# Controller_Board_Main.net
KiCad netlist of a schematic drawn in Altium Designer
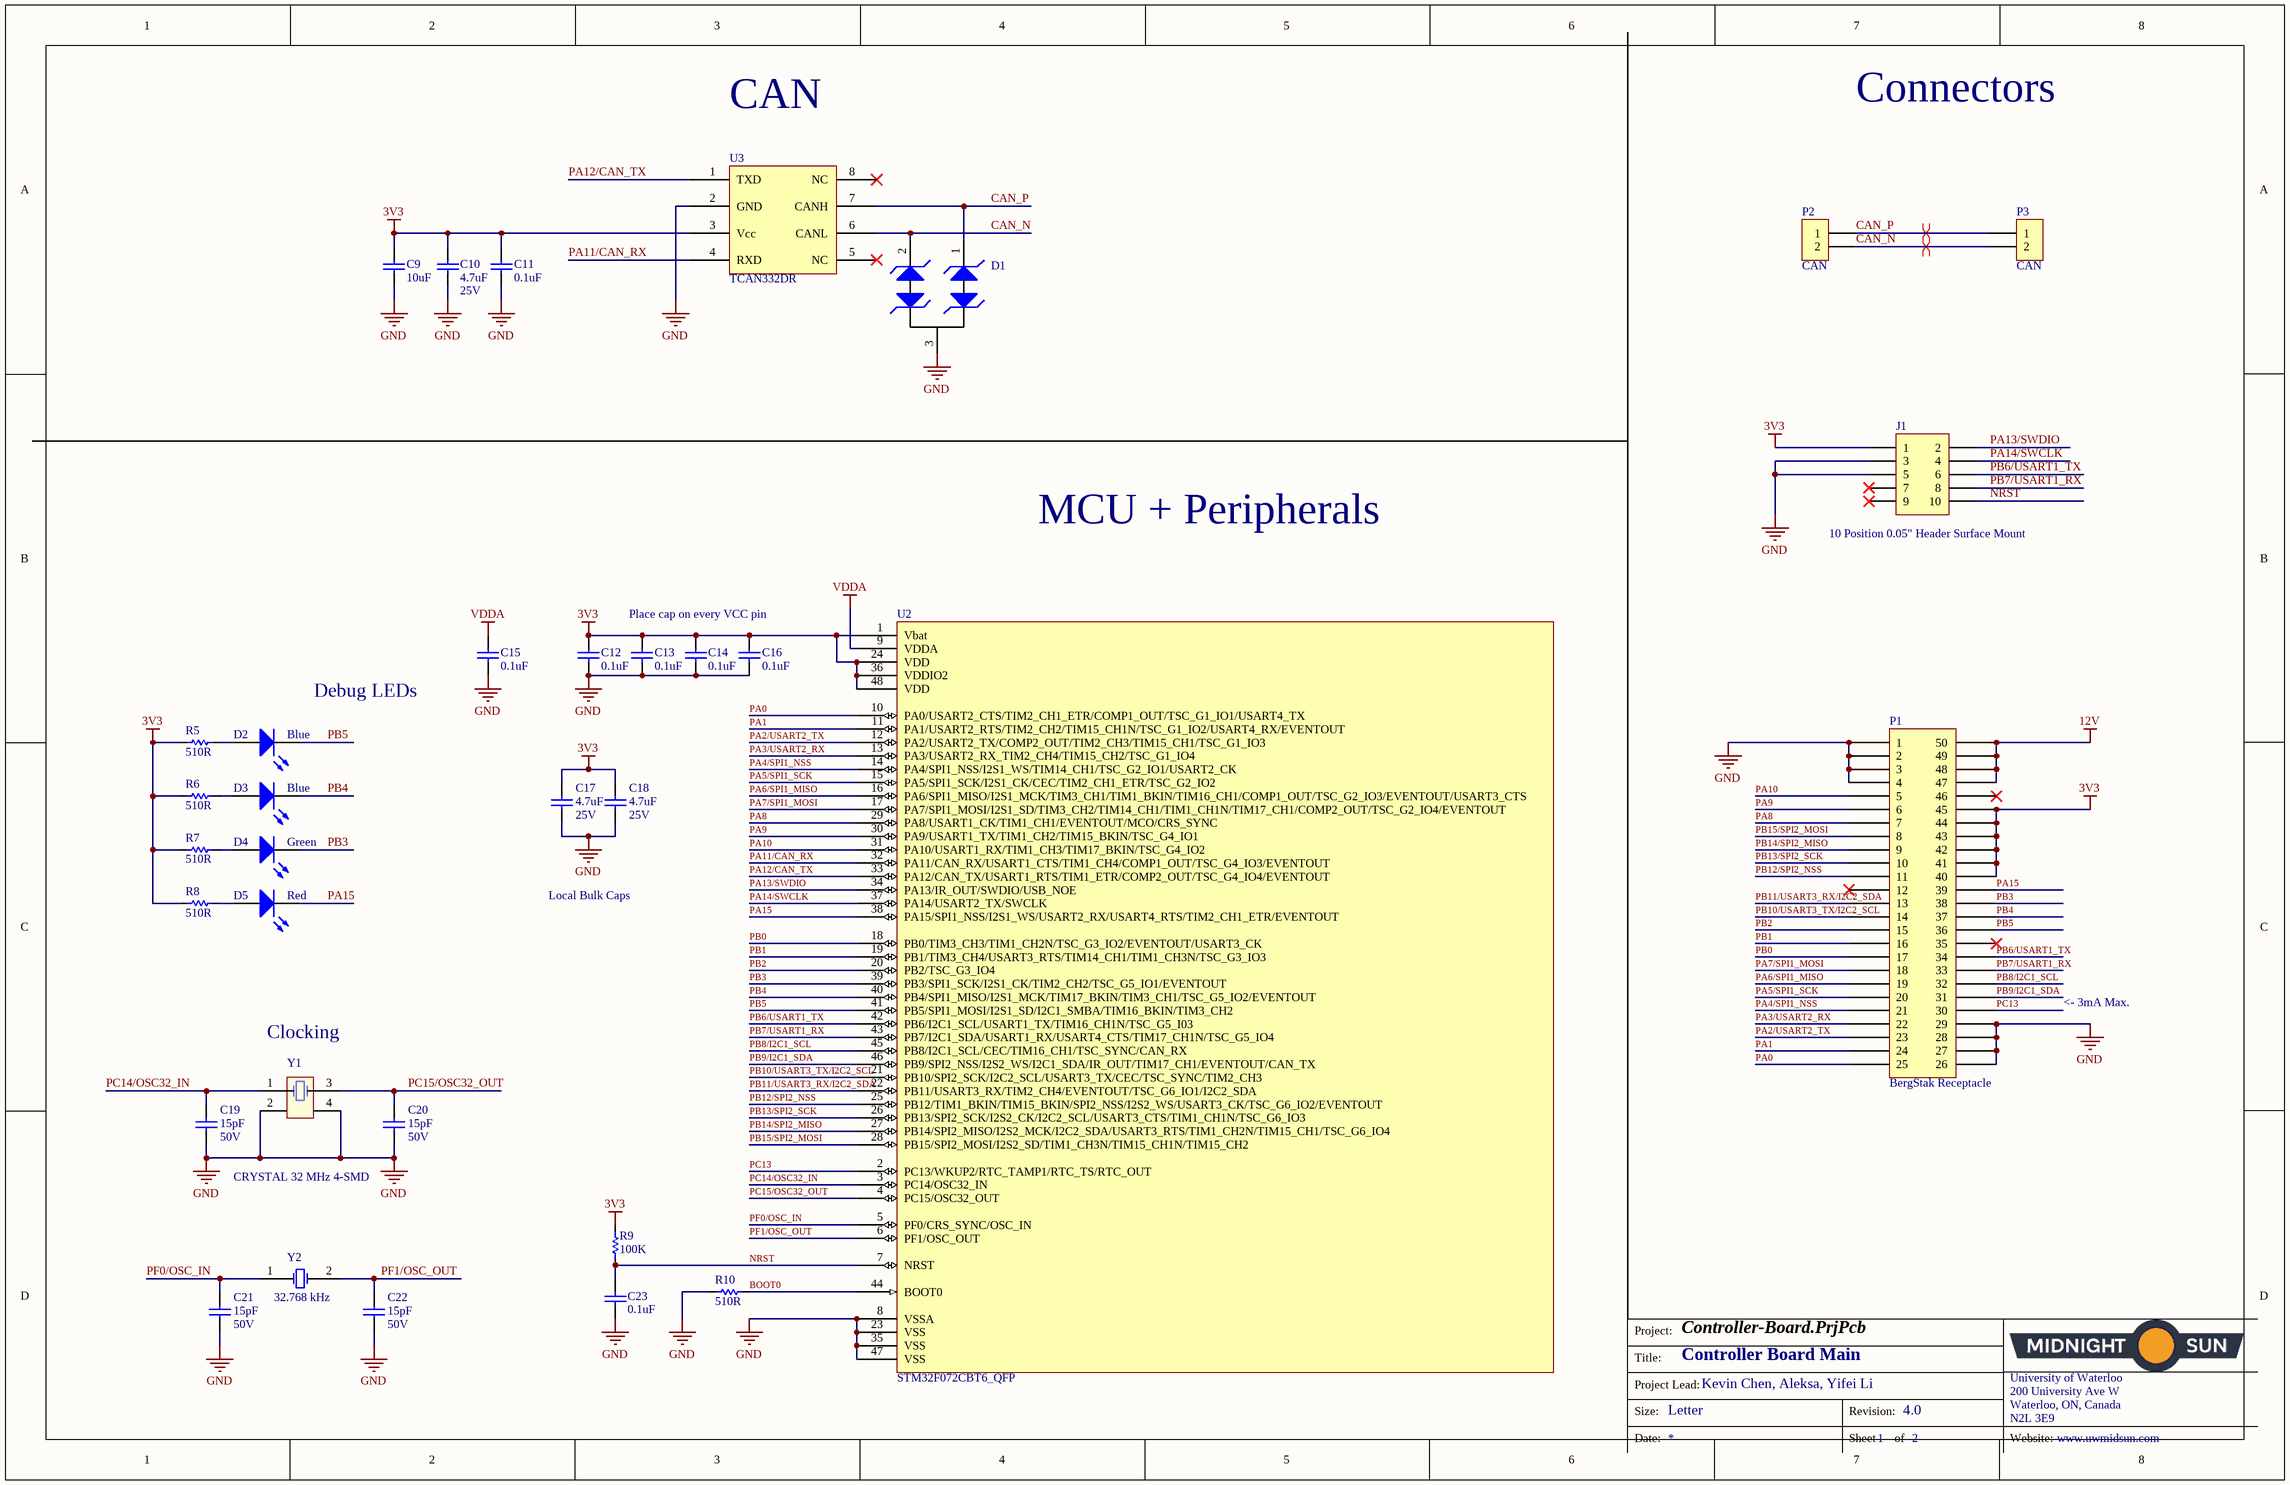
[diagram p0: Controller_Board_Main.SchDoc]

(export (version "E")
  (design (tool "Eeschema 10.0.6"))
  (components
    (comp (ref "C9")
      (value "10uF")
      (footprint "CAPC1608X06N")
      (description "10µF ±20% 25V Ceramic Capacitor X5R 0603 (1608 Metric)")
      (fields
        (field (name "MANUFACTURER") "Murata Electronics North America")
        (field (name "MANUFACTURERPARTNUMBER") "GRM188R61E106MA73D")
      )
      (libsource (lib "Midnight Sun Integrated Library") (part "CAP CER 10uF 25V 20% X5R 0603"))
    )
    (comp (ref "C10")
      (value "4.7uF")
      (footprint "CAPC1608X06N")
      (description "4.7µF ±10% 25V Ceramic Capacitor X5R 0603 (1608 Metric)")
      (fields
        (field (name "MANUFACTURER") "Murata Electronics North America")
        (field (name "MANUFACTURERPARTNUMBER") "GRM188R61E475KE11D")
        (field (name "VOLTAGE") "25V")
      )
      (libsource (lib "Midnight Sun Integrated Library") (part "CAP CER 4.7UF 25V 10% X5R 0603"))
    )
    (comp (ref "C11")
      (value "0.1uF")
      (footprint "CAPC1608X06N")
      (description "0.10µF ±10% 50V Ceramic Capacitor X7R 0603 (1608 Metric)")
      (fields
        (field (name "MANUFACTURER") "AVX Corporation")
        (field (name "MANUFACTURERPARTNUMBER") "06035C104KAT2A")
      )
      (libsource (lib "Midnight Sun Integrated Library") (part "CAP CER 0.1UF 50V 10% X7R 0603"))
    )
    (comp (ref "C12")
      (value "0.1uF")
      (footprint "CAPC1608X06N")
      (description "0.10µF ±10% 50V Ceramic Capacitor X7R 0603 (1608 Metric)")
      (fields
        (field (name "MANUFACTURER") "AVX Corporation")
        (field (name "MANUFACTURERPARTNUMBER") "06035C104KAT2A")
      )
      (libsource (lib "Midnight Sun Integrated Library") (part "CAP CER 0.1UF 50V 10% X7R 0603"))
    )
    (comp (ref "C13")
      (value "0.1uF")
      (footprint "CAPC1608X06N")
      (description "0.10µF ±10% 50V Ceramic Capacitor X7R 0603 (1608 Metric)")
      (fields
        (field (name "MANUFACTURER") "AVX Corporation")
        (field (name "MANUFACTURERPARTNUMBER") "06035C104KAT2A")
      )
      (libsource (lib "Midnight Sun Integrated Library") (part "CAP CER 0.1UF 50V 10% X7R 0603"))
    )
    (comp (ref "C14")
      (value "0.1uF")
      (footprint "CAPC1608X06N")
      (description "0.10µF ±10% 50V Ceramic Capacitor X7R 0603 (1608 Metric)")
      (fields
        (field (name "MANUFACTURER") "AVX Corporation")
        (field (name "MANUFACTURERPARTNUMBER") "06035C104KAT2A")
      )
      (libsource (lib "Midnight Sun Integrated Library") (part "CAP CER 0.1UF 50V 10% X7R 0603"))
    )
    (comp (ref "C15")
      (value "0.1uF")
      (footprint "CAP, 0603")
      (description "0.10µF ±10% 50V Ceramic Capacitor X7R 0603 (1608 Metric)")
      (fields
        (field (name "MANUFACTURER") "AVX Corporation")
        (field (name "MANUFACTURERPARTNUMBER") "06035C104KAT2A")
      )
      (libsource (lib "Midnight Sun Integrated Library") (part "CAP CER 0.1UF 50V 10% X7R 0603"))
    )
    (comp (ref "C16")
      (value "0.1uF")
      (footprint "CAPC1608X06N")
      (description "0.10µF ±10% 50V Ceramic Capacitor X7R 0603 (1608 Metric)")
      (fields
        (field (name "MANUFACTURER") "AVX Corporation")
        (field (name "MANUFACTURERPARTNUMBER") "06035C104KAT2A")
      )
      (libsource (lib "Midnight Sun Integrated Library") (part "CAP CER 0.1UF 50V 10% X7R 0603"))
    )
    (comp (ref "C17")
      (value "4.7uF")
      (footprint "CAPC1608X06N")
      (description "4.7µF ±10% 25V Ceramic Capacitor X5R 0603 (1608 Metric)")
      (fields
        (field (name "MANUFACTURER") "Murata Electronics North America")
        (field (name "MANUFACTURERPARTNUMBER") "GRM188R61E475KE11D")
        (field (name "VOLTAGE") "25V")
      )
      (libsource (lib "Midnight Sun Integrated Library") (part "CAP CER 4.7UF 25V 10% X5R 0603"))
    )
    (comp (ref "C18")
      (value "4.7uF")
      (footprint "CAPC1608X06N")
      (description "4.7µF ±10% 25V Ceramic Capacitor X5R 0603 (1608 Metric)")
      (fields
        (field (name "MANUFACTURER") "Murata Electronics North America")
        (field (name "MANUFACTURERPARTNUMBER") "GRM188R61E475KE11D")
        (field (name "VOLTAGE") "25V")
      )
      (libsource (lib "Midnight Sun Integrated Library") (part "CAP CER 4.7UF 25V 10% X5R 0603"))
    )
    (comp (ref "C19")
      (value "15pF")
      (footprint "CAPC1608X06N")
      (description "15pF ±5% 50V Ceramic Capacitor C0G, NP0 0603 (1608 Metric)")
      (fields
        (field (name "MANUFACTURER") "Yageo")
        (field (name "MANUFACTURERPARTNUMBER") "CC0603JRNPO9BN150")
        (field (name "VOLTAGE") "50V")
      )
      (libsource (lib "Midnight Sun Integrated Library") (part "CAP CER 15PF 50V NPO 0603"))
    )
    (comp (ref "C20")
      (value "15pF")
      (footprint "CAPC1608X06N")
      (description "15pF ±5% 50V Ceramic Capacitor C0G, NP0 0603 (1608 Metric)")
      (fields
        (field (name "MANUFACTURER") "Yageo")
        (field (name "MANUFACTURERPARTNUMBER") "CC0603JRNPO9BN150")
        (field (name "VOLTAGE") "50V")
      )
      (libsource (lib "Midnight Sun Integrated Library") (part "CAP CER 15PF 50V NPO 0603"))
    )
    (comp (ref "C21")
      (value "15pF")
      (footprint "CAPC1608X06N")
      (description "15pF ±5% 50V Ceramic Capacitor C0G, NP0 0603 (1608 Metric)")
      (fields
        (field (name "MANUFACTURER") "Yageo")
        (field (name "MANUFACTURERPARTNUMBER") "CC0603JRNPO9BN150")
        (field (name "VOLTAGE") "50V")
      )
      (libsource (lib "Midnight Sun Integrated Library") (part "CAP CER 15PF 50V NPO 0603"))
    )
    (comp (ref "C22")
      (value "15pF")
      (footprint "CAPC1608X06N")
      (description "15pF ±5% 50V Ceramic Capacitor C0G, NP0 0603 (1608 Metric)")
      (fields
        (field (name "MANUFACTURER") "Yageo")
        (field (name "MANUFACTURERPARTNUMBER") "CC0603JRNPO9BN150")
        (field (name "VOLTAGE") "50V")
      )
      (libsource (lib "Midnight Sun Integrated Library") (part "CAP CER 15PF 50V NPO 0603"))
    )
    (comp (ref "C23")
      (value "0.1uF")
      (footprint "CAPC1608X06N")
      (description "0.10µF ±10% 50V Ceramic Capacitor X7R 0603 (1608 Metric)")
      (fields
        (field (name "MANUFACTURER") "AVX Corporation")
        (field (name "MANUFACTURERPARTNUMBER") "06035C104KAT2A")
      )
      (libsource (lib "Midnight Sun Integrated Library") (part "CAP CER 0.1UF 50V 10% X7R 0603"))
    )
    (comp (ref "D1")
      (value "TVS Diode")
      (footprint "SOT23")
      (description "TVS DIODE 24VWM 70VC SOT23")
      (libsource (lib "Midnight Sun Integrated Library") (part "TVS Diode"))
    )
    (comp (ref "D2")
      (value "Blue")
      (footprint "DIOC1608X06N")
      (description "LED BLUE CLEAR 0603 SMD")
      (fields
        (field (name "DIGIKEY PART NUMBER") "160-1827-1-ND")
        (field (name "MANUFACTURER") "Lite-On Inc.")
      )
      (libsource (lib "Midnight Sun Integrated Library") (part "LED_BLUE"))
    )
    (comp (ref "D3")
      (value "Blue")
      (footprint "DIOC1608X06N")
      (description "LED BLUE CLEAR 0603 SMD")
      (fields
        (field (name "DIGIKEY PART NUMBER") "160-1827-1-ND")
        (field (name "MANUFACTURER") "Lite-On Inc.")
      )
      (libsource (lib "Midnight Sun Integrated Library") (part "LED_BLUE"))
    )
    (comp (ref "D4")
      (value "Green")
      (footprint "DIOC1608X06N")
      (description "LED GREEN CLEAR 0603 SMD")
      (fields
        (field (name "MANUFACTURER") "Lite-On Inc.")
        (field (name "MANUFACTURER PART NUMBER") "LTST-C193KGKT-5A")
      )
      (libsource (lib "Midnight Sun Integrated Library") (part "LED_GREEN"))
    )
    (comp (ref "D5")
      (value "Red")
      (footprint "DIOC1608X06N")
      (description "Red LED 0603")
      (fields (field (name "MANUFACTURE PART NUMBER") "LTST-C191KRKT"))
      (libsource (lib "Midnight Sun Integrated Library") (part "LED_RED"))
    )
    (comp (ref "J1")
      (value "10 Position 0.05\" Header Surface Mount")
      (footprint "10 POS 1.27MM RECT CONN")
      (description "10 Positions Header Connector 0.050\" (1.27mm) Surface Mount Gold")
      (fields
        (field (name "MANUFACTURER") "Amphenol FCI")
        (field (name "MANUFACTURER PART NUMBER") "20021121-00010C4LF")
      )
      (libsource (lib "Midnight Sun Integrated Library") (part "10 Position 0.05{dblquote} Header Surface Mount"))
    )
    (comp (ref "P1")
      (value "BergStak Receptacle")
      (footprint "Bergstak 50 Pos Receptacle")
      (description "50 Position Connector Receptacle, Center Strip Contacts Surface Mount Gold")
      (fields
        (field (name "DIGIKEY PART NUMBER") "609-5227-1-ND")
        (field (name "MANUFACTURER PART NUMBER") "10132798-052100LF")
      )
      (libsource (lib "Midnight Sun Integrated Library") (part "BergStak 50 Position Connector Receptacle"))
    )
    (comp (ref "P2")
      (value "CAN")
      (footprint "2 POS Dura-Click")
      (description "2 Positions Header, Shrouded Connector 0.079\" (2.00mm) Surface Mount, Right Angle Tin")
      (fields (field (name "MANUFACTURER") "Molex") (field (name "MANUFACTURER PART NUMBER") "5023520200"))
      (libsource (lib "") (part "2 Position DuraClik CAN Connector_1"))
    )
    (comp (ref "P3")
      (value "CAN")
      (footprint "2 POS Dura-Click")
      (description "2 Positions Header, Shrouded Connector 0.079\" (2.00mm) Surface Mount, Right Angle Tin")
      (fields (field (name "MANUFACTURER") "Molex") (field (name "MANUFACTURER PART NUMBER") "5023520200"))
      (libsource (lib "Midnight Sun Integrated Library") (part "2 Position DuraClik CAN Connector"))
    )
    (comp (ref "R5")
      (value "510R")
      (footprint "RESC1608X06N")
      (description "RES SMD 510 OHM 5% 1/10W 0603")
      (fields
        (field (name "MANUFACTURERPARTNUMBER") "RC0603JR-07510RL")
        (field (name "MANUFACTURER") "Yageo")
      )
      (libsource (lib "Midnight Sun Integrated Library") (part "RES 510 OHM 1/10W 0603 SMD"))
    )
    (comp (ref "R6")
      (value "510R")
      (footprint "RESC1608X06N")
      (description "RES SMD 510 OHM 5% 1/10W 0603")
      (fields
        (field (name "MANUFACTURERPARTNUMBER") "RC0603JR-07510RL")
        (field (name "MANUFACTURER") "Yageo")
      )
      (libsource (lib "Midnight Sun Integrated Library") (part "RES 510 OHM 1/10W 0603 SMD"))
    )
    (comp (ref "R7")
      (value "510R")
      (footprint "RESC1608X06N")
      (description "RES SMD 510 OHM 5% 1/10W 0603")
      (fields
        (field (name "MANUFACTURERPARTNUMBER") "RC0603JR-07510RL")
        (field (name "MANUFACTURER") "Yageo")
      )
      (libsource (lib "Midnight Sun Integrated Library") (part "RES 510 OHM 1/10W 0603 SMD"))
    )
    (comp (ref "R8")
      (value "510R")
      (footprint "RESC1608X06N")
      (description "RES SMD 510 OHM 5% 1/10W 0603")
      (fields
        (field (name "MANUFACTURERPARTNUMBER") "RC0603JR-07510RL")
        (field (name "MANUFACTURER") "Yageo")
      )
      (libsource (lib "Midnight Sun Integrated Library") (part "RES 510 OHM 1/10W 0603 SMD"))
    )
    (comp (ref "R9")
      (value "100K")
      (footprint "RESC1608X06N")
      (description "RES SMD 100K OHM 5% 1/10W 0603")
      (fields
        (field (name "MANUFACTURERPARTNUMBER") "RC0603JR-07100KL")
        (field (name "MANUFACTURER") "Yageo")
      )
      (libsource (lib "Midnight Sun Integrated Library") (part "RES 100K OHM 1/8W 5% 0603 SMD"))
    )
    (comp (ref "R10")
      (value "510R")
      (footprint "RESC1608X06N")
      (description "RES SMD 510 OHM 5% 1/10W 0603")
      (fields
        (field (name "MANUFACTURERPARTNUMBER") "RC0603JR-07510RL")
        (field (name "MANUFACTURER") "Yageo")
      )
      (libsource (lib "Midnight Sun Integrated Library") (part "RES 510 OHM 1/10W 0603 SMD"))
    )
    (comp (ref "U2")
      (value "STM32F072CBT6_QFP")
      (footprint "TSQFP50P890X890X160-48M")
      (fields
        (field (name "DIGIKEY PART NUMBER") "497-14645-ND")
        (field (name "MANUFACTURER PART NUMBER") "STM32F072CBT6")
      )
      (libsource (lib "Midnight Sun Integrated Library") (part "STM32F072CBT6_QFP"))
    )
    (comp (ref "U3")
      (value "TCAN332DR CAN Transceiver_SOT")
      (footprint "TSOP65P280X145-8N")
      (description "1/1 Transceiver CAN 8-SOIC")
      (fields
        (field (name "DIGIKEY PART NUMBER") "296-43711-1-ND")
        (field (name "MANUFACTURER PART NUMBER") "TCAN332DR")
      )
      (libsource (lib "Midnight Sun Integrated Library") (part "TCAN332DR CAN Transceiver_SOT"))
    )
    (comp (ref "Y1")
      (value "CRYSTAL 32 MHz 4-SMD")
      (footprint "CX2520DB CRYSTAL")
      (description "32MHz ±15ppm Crystal 8pF 50 Ohm -40°C ~ 85°C AEC-Q200 Surface Mount 4-SMD, No Lead")
      (libsource (lib "Midnight Sun Integrated Library") (part "CRYSTAL 32 MHz 4-SMD"))
    )
    (comp (ref "Y2")
      (value "32.768 kHz")
      (footprint "ABS07AIG CRYSTAL")
      (description "32.768kHz ±20ppm Crystal 6pF 50 kOhm -40°C ~ 85°C Surface Mount 4-SOJ, 5.50mm pitch")
      (fields (field (name "MANUFACTURER PART NUMBER") "ABS07AIG-32.768KHZ-9-1-T"))
      (libsource (lib "Midnight Sun Integrated Library") (part "CRYSTAL 32.768KHZ 9PF 2-SMD"))
    )
  )
  (nets
    (net (code "1") (name "/BOOT0") (class "Default")
      (node (ref "R10") (pin "2") (pinfunction "2_2") (pintype "passive"))
      (node (ref "U2") (pin "44") (pinfunction "BOOT0_44") (pintype "input"))
    )
    (net (code "2") (name "/CAN_N") (class "Default")
      (node (ref "D1") (pin "2") (pinfunction "Cathode2_2") (pintype "passive"))
      (node (ref "P2") (pin "2") (pinfunction "2_2") (pintype "passive"))
      (node (ref "P3") (pin "2") (pinfunction "2_2") (pintype "passive"))
      (node (ref "U3") (pin "6") (pinfunction "CANL_6") (pintype "passive"))
    )
    (net (code "3") (name "/CAN_P") (class "Default")
      (node (ref "D1") (pin "1") (pinfunction "Cathode1_1") (pintype "passive"))
      (node (ref "P2") (pin "1") (pinfunction "1_1") (pintype "passive"))
      (node (ref "P3") (pin "1") (pinfunction "1_1") (pintype "passive"))
      (node (ref "U3") (pin "7") (pinfunction "CANH_7") (pintype "passive"))
    )
    (net (code "4") (name "/NRST") (class "Default")
      (node (ref "C23") (pin "2") (pinfunction "2_2") (pintype "passive"))
      (node (ref "J1") (pin "10") (pinfunction "10_10") (pintype "passive"))
      (node (ref "R9") (pin "1") (pinfunction "1_1") (pintype "passive"))
      (node (ref "U2") (pin "7") (pinfunction "NRST_7") (pintype "bidirectional"))
    )
    (net (code "5") (name "/PA0") (class "Default")
      (node (ref "P1") (pin "25") (pinfunction "25_25") (pintype "passive"))
      (node (ref "U2") (pin "10") (pinfunction "PA0/USART2_CTS/TIM2_CH1_ETR/COMP1_OUT/TSC_G1_IO1/USART4_TX_10") (pintype "bidirectional"))
    )
    (net (code "6") (name "/PA1") (class "Default")
      (node (ref "P1") (pin "24") (pinfunction "24_24") (pintype "passive"))
      (node (ref "U2") (pin "11") (pinfunction "PA1/USART2_RTS/TIM2_CH2/TIM15_CH1N/TSC_G1_IO2/USART4_RX/EVENTOUT_11") (pintype "bidirectional"))
    )
    (net (code "7") (name "/PA2{slash}USART2_TX") (class "Default")
      (node (ref "P1") (pin "23") (pinfunction "23_23") (pintype "passive"))
      (node (ref "U2") (pin "12") (pinfunction "PA2/USART2_TX/COMP2_OUT/TIM2_CH3/TIM15_CH1/TSC_G1_IO3_12") (pintype "bidirectional"))
    )
    (net (code "8") (name "/PA3{slash}USART2_RX") (class "Default")
      (node (ref "P1") (pin "22") (pinfunction "22_22") (pintype "passive"))
      (node (ref "U2") (pin "13") (pinfunction "PA3/USART2_RX_TIM2_CH4/TIM15_CH2/TSC_G1_IO4_13") (pintype "bidirectional"))
    )
    (net (code "9") (name "/PA4{slash}SPI1_NSS") (class "Default")
      (node (ref "P1") (pin "21") (pinfunction "21_21") (pintype "passive"))
      (node (ref "U2") (pin "14") (pinfunction "PA4/SPI1_NSS/I2S1_WS/TIM14_CH1/TSC_G2_IO1/USART2_CK_14") (pintype "bidirectional"))
    )
    (net (code "10") (name "/PA5{slash}SPI1_SCK") (class "Default")
      (node (ref "P1") (pin "20") (pinfunction "20_20") (pintype "passive"))
      (node (ref "U2") (pin "15") (pinfunction "PA5/SPI1_SCK/I2S1_CK/CEC/TIM2_CH1_ETR/TSC_G2_IO2_15") (pintype "bidirectional"))
    )
    (net (code "11") (name "/PA6{slash}SPI1_MISO") (class "Default")
      (node (ref "P1") (pin "19") (pinfunction "19_19") (pintype "passive"))
      (node (ref "U2") (pin "16") (pinfunction "PA6/SPI1_MISO/I2S1_MCK/TIM3_CH1/TIM1_BKIN/TIM16_CH1/COMP1_OUT/TSC_G2_IO3/EVENTOUT/USART3_CTS_16") (pintype "bidirectional"))
    )
    (net (code "12") (name "/PA7{slash}SPI1_MOSI") (class "Default")
      (node (ref "P1") (pin "18") (pinfunction "18_18") (pintype "passive"))
      (node (ref "U2") (pin "17") (pinfunction "PA7/SPI1_MOSI/I2S1_SD/TIM3_CH2/TIM14_CH1/TIM1_CH1N/TIM17_CH1/COMP2_OUT/TSC_G2_IO4/EVENTOUT_17") (pintype "bidirectional"))
    )
    (net (code "13") (name "/PA8") (class "Default")
      (node (ref "P1") (pin "7") (pinfunction "7_7") (pintype "passive"))
      (node (ref "U2") (pin "29") (pinfunction "PA8/USART1_CK/TIM1_CH1/EVENTOUT/MCO/CRS_SYNC_29") (pintype "bidirectional"))
    )
    (net (code "14") (name "/PA9") (class "Default")
      (node (ref "P1") (pin "6") (pinfunction "6_6") (pintype "passive"))
      (node (ref "U2") (pin "30") (pinfunction "PA9/USART1_TX/TIM1_CH2/TIM15_BKIN/TSC_G4_IO1_30") (pintype "bidirectional"))
    )
    (net (code "15") (name "/PA10") (class "Default")
      (node (ref "P1") (pin "5") (pinfunction "5_5") (pintype "passive"))
      (node (ref "U2") (pin "31") (pinfunction "PA10/USART1_RX/TIM1_CH3/TIM17_BKIN/TSC_G4_IO2_31") (pintype "bidirectional"))
    )
    (net (code "16") (name "/PA11{slash}CAN_RX") (class "Default")
      (node (ref "U2") (pin "32") (pinfunction "PA11/CAN_RX/USART1_CTS/TIM1_CH4/COMP1_OUT/TSC_G4_IO3/EVENTOUT_32") (pintype "bidirectional"))
      (node (ref "U3") (pin "4") (pinfunction "RXD_4") (pintype "passive"))
    )
    (net (code "17") (name "/PA12{slash}CAN_TX") (class "Default")
      (node (ref "U2") (pin "33") (pinfunction "PA12/CAN_TX/USART1_RTS/TIM1_ETR/COMP2_OUT/TSC_G4_IO4/EVENTOUT_33") (pintype "bidirectional"))
      (node (ref "U3") (pin "1") (pinfunction "TXD_1") (pintype "passive"))
    )
    (net (code "18") (name "/PA13{slash}SWDIO") (class "Default")
      (node (ref "J1") (pin "2") (pinfunction "2_2") (pintype "passive"))
      (node (ref "U2") (pin "34") (pinfunction "PA13/IR_OUT/SWDIO/USB_NOE_34") (pintype "bidirectional"))
    )
    (net (code "19") (name "/PA14{slash}SWCLK") (class "Default")
      (node (ref "J1") (pin "4") (pinfunction "4_4") (pintype "passive"))
      (node (ref "U2") (pin "37") (pinfunction "PA14/USART2_TX/SWCLK_37") (pintype "bidirectional"))
    )
    (net (code "20") (name "/PA15") (class "Default")
      (node (ref "D5") (pin "2") (pinfunction "K_2") (pintype "passive"))
      (node (ref "P1") (pin "39") (pinfunction "39_39") (pintype "passive"))
      (node (ref "U2") (pin "38") (pinfunction "PA15/SPI1_NSS/I2S1_WS/USART2_RX/USART4_RTS/TIM2_CH1_ETR/EVENTOUT_38") (pintype "bidirectional"))
    )
    (net (code "21") (name "/PB0") (class "Default")
      (node (ref "P1") (pin "17") (pinfunction "17_17") (pintype "passive"))
      (node (ref "U2") (pin "18") (pinfunction "PB0/TIM3_CH3/TIM1_CH2N/TSC_G3_IO2/EVENTOUT/USART3_CK_18") (pintype "bidirectional"))
    )
    (net (code "22") (name "/PB1") (class "Default")
      (node (ref "P1") (pin "16") (pinfunction "16_16") (pintype "passive"))
      (node (ref "U2") (pin "19") (pinfunction "PB1/TIM3_CH4/USART3_RTS/TIM14_CH1/TIM1_CH3N/TSC_G3_IO3_19") (pintype "bidirectional"))
    )
    (net (code "23") (name "/PB2") (class "Default")
      (node (ref "P1") (pin "15") (pinfunction "15_15") (pintype "passive"))
      (node (ref "U2") (pin "20") (pinfunction "PB2/TSC_G3_IO4_20") (pintype "bidirectional"))
    )
    (net (code "24") (name "/PB3") (class "Default")
      (node (ref "D4") (pin "2") (pinfunction "K_2") (pintype "passive"))
      (node (ref "P1") (pin "38") (pinfunction "38_38") (pintype "passive"))
      (node (ref "U2") (pin "39") (pinfunction "PB3/SPI1_SCK/I2S1_CK/TIM2_CH2/TSC_G5_IO1/EVENTOUT_39") (pintype "bidirectional"))
    )
    (net (code "25") (name "/PB4") (class "Default")
      (node (ref "D3") (pin "2") (pinfunction "K_2") (pintype "passive"))
      (node (ref "P1") (pin "37") (pinfunction "37_37") (pintype "passive"))
      (node (ref "U2") (pin "40") (pinfunction "PB4/SPI1_MISO/I2S1_MCK/TIM17_BKIN/TIM3_CH1/TSC_G5_IO2/EVENTOUT_40") (pintype "bidirectional"))
    )
    (net (code "26") (name "/PB5") (class "Default")
      (node (ref "D2") (pin "2") (pinfunction "K_2") (pintype "passive"))
      (node (ref "P1") (pin "36") (pinfunction "36_36") (pintype "passive"))
      (node (ref "U2") (pin "41") (pinfunction "PB5/SPI1_MOSI/I2S1_SD/I2C1_SMBA/TIM16_BKIN/TIM3_CH2_41") (pintype "bidirectional"))
    )
    (net (code "27") (name "/PB6{slash}USART1_TX") (class "Default")
      (node (ref "J1") (pin "6") (pinfunction "6_6") (pintype "passive"))
      (node (ref "P1") (pin "34") (pinfunction "34_34") (pintype "passive"))
      (node (ref "U2") (pin "42") (pinfunction "PB6/I2C1_SCL/USART1_TX/TIM16_CH1N/TSC_G5_I03_42") (pintype "bidirectional"))
    )
    (net (code "28") (name "/PB7{slash}USART1_RX") (class "Default")
      (node (ref "J1") (pin "8") (pinfunction "8_8") (pintype "passive"))
      (node (ref "P1") (pin "33") (pinfunction "33_33") (pintype "passive"))
      (node (ref "U2") (pin "43") (pinfunction "PB7/I2C1_SDA/USART1_RX/USART4_CTS/TIM17_CH1N/TSC_G5_IO4_43") (pintype "bidirectional"))
    )
    (net (code "29") (name "/PB8{slash}I2C1_SCL") (class "Default")
      (node (ref "P1") (pin "32") (pinfunction "32_32") (pintype "passive"))
      (node (ref "U2") (pin "45") (pinfunction "PB8/I2C1_SCL/CEC/TIM16_CH1/TSC_SYNC/CAN_RX_45") (pintype "bidirectional"))
    )
    (net (code "30") (name "/PB9{slash}I2C1_SDA") (class "Default")
      (node (ref "P1") (pin "31") (pinfunction "31_31") (pintype "passive"))
      (node (ref "U2") (pin "46") (pinfunction "PB9/SPI2_NSS/I2S2_WS/I2C1_SDA/IR_OUT/TIM17_CH1/EVENTOUT/CAN_TX_46") (pintype "bidirectional"))
    )
    (net (code "31") (name "/PB10{slash}USART3_TX{slash}I2C2_SCL") (class "Default")
      (node (ref "P1") (pin "14") (pinfunction "14_14") (pintype "passive"))
      (node (ref "U2") (pin "21") (pinfunction "PB10/SPI2_SCK/I2C2_SCL/USART3_TX/CEC/TSC_SYNC/TIM2_CH3_21") (pintype "bidirectional"))
    )
    (net (code "32") (name "/PB11{slash}USART3_RX{slash}I2C2_SDA") (class "Default")
      (node (ref "P1") (pin "13") (pinfunction "13_13") (pintype "passive"))
      (node (ref "U2") (pin "22") (pinfunction "PB11/USART3_RX/TIM2_CH4/EVENTOUT/TSC_G6_IO1/I2C2_SDA_22") (pintype "bidirectional"))
    )
    (net (code "33") (name "/PB12{slash}SPI2_NSS") (class "Default")
      (node (ref "P1") (pin "11") (pinfunction "11_11") (pintype "passive"))
      (node (ref "U2") (pin "25") (pinfunction "PB12/TIM1_BKIN/TIM15_BKIN/SPI2_NSS/I2S2_WS/USART3_CK/TSC_G6_IO2/EVENTOUT_25") (pintype "bidirectional"))
    )
    (net (code "34") (name "/PB13{slash}SPI2_SCK") (class "Default")
      (node (ref "P1") (pin "10") (pinfunction "10_10") (pintype "passive"))
      (node (ref "U2") (pin "26") (pinfunction "PB13/SPI2_SCK/I2S2_CK/I2C2_SCL/USART3_CTS/TIM1_CH1N/TSC_G6_IO3_26") (pintype "bidirectional"))
    )
    (net (code "35") (name "/PB14{slash}SPI2_MISO") (class "Default")
      (node (ref "P1") (pin "9") (pinfunction "9_9") (pintype "passive"))
      (node (ref "U2") (pin "27") (pinfunction "PB14/SPI2_MISO/I2S2_MCK/I2C2_SDA/USART3_RTS/TIM1_CH2N/TIM15_CH1/TSC_G6_IO4_27") (pintype "bidirectional"))
    )
    (net (code "36") (name "/PB15{slash}SPI2_MOSI") (class "Default")
      (node (ref "P1") (pin "8") (pinfunction "8_8") (pintype "passive"))
      (node (ref "U2") (pin "28") (pinfunction "PB15/SPI2_MOSI/I2S2_SD/TIM1_CH3N/TIM15_CH1N/TIM15_CH2_28") (pintype "bidirectional"))
    )
    (net (code "37") (name "/PC13") (class "Default")
      (node (ref "P1") (pin "30") (pinfunction "30_30") (pintype "passive"))
      (node (ref "U2") (pin "2") (pinfunction "PC13/WKUP2/RTC_TAMP1/RTC_TS/RTC_OUT_2") (pintype "bidirectional"))
    )
    (net (code "38") (name "/PC14{slash}OSC32_IN") (class "Default")
      (node (ref "C19") (pin "2") (pinfunction "2_2") (pintype "passive"))
      (node (ref "U2") (pin "3") (pinfunction "PC14/OSC32_IN_3") (pintype "bidirectional"))
      (node (ref "Y1") (pin "1") (pinfunction "OSC1_1") (pintype "passive"))
    )
    (net (code "39") (name "/PC15{slash}OSC32_OUT") (class "Default")
      (node (ref "C20") (pin "2") (pinfunction "2_2") (pintype "passive"))
      (node (ref "U2") (pin "4") (pinfunction "PC15/OSC32_OUT_4") (pintype "bidirectional"))
      (node (ref "Y1") (pin "3") (pinfunction "OSC2_3") (pintype "passive"))
    )
    (net (code "40") (name "/PF0{slash}OSC_IN") (class "Default")
      (node (ref "C21") (pin "2") (pinfunction "2_2") (pintype "passive"))
      (node (ref "U2") (pin "5") (pinfunction "PF0/CRS_SYNC/OSC_IN_5") (pintype "bidirectional"))
      (node (ref "Y2") (pin "1") (pinfunction "1_1") (pintype "passive"))
    )
    (net (code "41") (name "/PF1{slash}OSC_OUT") (class "Default")
      (node (ref "C22") (pin "2") (pinfunction "2_2") (pintype "passive"))
      (node (ref "U2") (pin "6") (pinfunction "PF1/OSC_OUT_6") (pintype "bidirectional"))
      (node (ref "Y2") (pin "2") (pinfunction "2_2") (pintype "passive"))
    )
    (net (code "42") (name "3V3") (class "Default")
      (node (ref "C10") (pin "2") (pinfunction "2_2") (pintype "passive"))
      (node (ref "C11") (pin "2") (pinfunction "2_2") (pintype "passive"))
      (node (ref "C12") (pin "2") (pinfunction "2_2") (pintype "passive"))
      (node (ref "C13") (pin "2") (pinfunction "2_2") (pintype "passive"))
      (node (ref "C14") (pin "2") (pinfunction "2_2") (pintype "passive"))
      (node (ref "C16") (pin "2") (pinfunction "2_2") (pintype "passive"))
      (node (ref "C17") (pin "2") (pinfunction "2_2") (pintype "passive"))
      (node (ref "C18") (pin "2") (pinfunction "2_2") (pintype "passive"))
      (node (ref "C9") (pin "2") (pinfunction "2_2") (pintype "passive"))
      (node (ref "J1") (pin "1") (pinfunction "1_1") (pintype "passive"))
      (node (ref "P1") (pin "40") (pinfunction "40_40") (pintype "passive"))
      (node (ref "P1") (pin "41") (pinfunction "41_41") (pintype "passive"))
      (node (ref "P1") (pin "42") (pinfunction "42_42") (pintype "passive"))
      (node (ref "P1") (pin "43") (pinfunction "43_43") (pintype "passive"))
      (node (ref "P1") (pin "44") (pinfunction "44_44") (pintype "passive"))
      (node (ref "P1") (pin "45") (pinfunction "45_45") (pintype "passive"))
      (node (ref "R5") (pin "1") (pinfunction "1_1") (pintype "passive"))
      (node (ref "R6") (pin "1") (pinfunction "1_1") (pintype "passive"))
      (node (ref "R7") (pin "1") (pinfunction "1_1") (pintype "passive"))
      (node (ref "R8") (pin "1") (pinfunction "1_1") (pintype "passive"))
      (node (ref "R9") (pin "2") (pinfunction "2_2") (pintype "passive"))
      (node (ref "U2") (pin "1") (pinfunction "Vbat_1") (pintype "power_in"))
      (node (ref "U2") (pin "24") (pinfunction "VDD_24") (pintype "power_in"))
      (node (ref "U2") (pin "36") (pinfunction "VDDIO2_36") (pintype "power_in"))
      (node (ref "U2") (pin "48") (pinfunction "VDD_48") (pintype "power_in"))
      (node (ref "U3") (pin "3") (pinfunction "Vcc_3") (pintype "passive"))
    )
    (net (code "43") (name "12V") (class "Default")
      (node (ref "P1") (pin "47") (pinfunction "47_47") (pintype "passive"))
      (node (ref "P1") (pin "48") (pinfunction "48_48") (pintype "passive"))
      (node (ref "P1") (pin "49") (pinfunction "49_49") (pintype "passive"))
      (node (ref "P1") (pin "50") (pinfunction "50_50") (pintype "passive"))
    )
    (net (code "44") (name "GND") (class "Default")
      (node (ref "C10") (pin "1") (pinfunction "1_1") (pintype "passive"))
      (node (ref "C11") (pin "1") (pinfunction "1_1") (pintype "passive"))
      (node (ref "C12") (pin "1") (pinfunction "1_1") (pintype "passive"))
      (node (ref "C13") (pin "1") (pinfunction "1_1") (pintype "passive"))
      (node (ref "C14") (pin "1") (pinfunction "1_1") (pintype "passive"))
      (node (ref "C15") (pin "1") (pinfunction "1_1") (pintype "passive"))
      (node (ref "C16") (pin "1") (pinfunction "1_1") (pintype "passive"))
      (node (ref "C17") (pin "1") (pinfunction "1_1") (pintype "passive"))
      (node (ref "C18") (pin "1") (pinfunction "1_1") (pintype "passive"))
      (node (ref "C19") (pin "1") (pinfunction "1_1") (pintype "passive"))
      (node (ref "C20") (pin "1") (pinfunction "1_1") (pintype "passive"))
      (node (ref "C21") (pin "1") (pinfunction "1_1") (pintype "passive"))
      (node (ref "C22") (pin "1") (pinfunction "1_1") (pintype "passive"))
      (node (ref "C23") (pin "1") (pinfunction "1_1") (pintype "passive"))
      (node (ref "C9") (pin "1") (pinfunction "1_1") (pintype "passive"))
      (node (ref "D1") (pin "3") (pinfunction "Common_Cathode_3") (pintype "power_in"))
      (node (ref "J1") (pin "3") (pinfunction "3_3") (pintype "passive"))
      (node (ref "J1") (pin "5") (pinfunction "5_5") (pintype "passive"))
      (node (ref "P1") (pin "1") (pinfunction "1_1") (pintype "passive"))
      (node (ref "P1") (pin "2") (pinfunction "2_2") (pintype "passive"))
      (node (ref "P1") (pin "26") (pinfunction "26_26") (pintype "passive"))
      (node (ref "P1") (pin "27") (pinfunction "27_27") (pintype "passive"))
      (node (ref "P1") (pin "28") (pinfunction "28_28") (pintype "passive"))
      (node (ref "P1") (pin "29") (pinfunction "29_29") (pintype "passive"))
      (node (ref "P1") (pin "3") (pinfunction "3_3") (pintype "passive"))
      (node (ref "P1") (pin "4") (pinfunction "4_4") (pintype "passive"))
      (node (ref "R10") (pin "1") (pinfunction "1_1") (pintype "passive"))
      (node (ref "U2") (pin "23") (pinfunction "VSS_23") (pintype "power_in"))
      (node (ref "U2") (pin "35") (pinfunction "VSS_35") (pintype "power_in"))
      (node (ref "U2") (pin "47") (pinfunction "VSS_47") (pintype "power_in"))
      (node (ref "U2") (pin "8") (pinfunction "VSSA_8") (pintype "power_in"))
      (node (ref "U3") (pin "2") (pinfunction "GND_2") (pintype "passive"))
      (node (ref "Y1") (pin "2") (pinfunction "2_2") (pintype "passive"))
      (node (ref "Y1") (pin "4") (pinfunction "3_4") (pintype "passive"))
    )
    (net (code "45") (name "Net-(D2-A)") (class "Default")
      (node (ref "D2") (pin "1") (pinfunction "A_1") (pintype "passive"))
      (node (ref "R5") (pin "2") (pinfunction "2_2") (pintype "passive"))
    )
    (net (code "46") (name "Net-(D3-A)") (class "Default")
      (node (ref "D3") (pin "1") (pinfunction "A_1") (pintype "passive"))
      (node (ref "R6") (pin "2") (pinfunction "2_2") (pintype "passive"))
    )
    (net (code "47") (name "Net-(D4-A)") (class "Default")
      (node (ref "D4") (pin "1") (pinfunction "A_1") (pintype "passive"))
      (node (ref "R7") (pin "2") (pinfunction "2_2") (pintype "passive"))
    )
    (net (code "48") (name "Net-(D5-A)") (class "Default")
      (node (ref "D5") (pin "1") (pinfunction "A_1") (pintype "passive"))
      (node (ref "R8") (pin "2") (pinfunction "2_2") (pintype "passive"))
    )
    (net (code "49") (name "VDDA") (class "Default")
      (node (ref "C15") (pin "2") (pinfunction "2_2") (pintype "passive"))
      (node (ref "U2") (pin "9") (pinfunction "VDDA_9") (pintype "power_in"))
    )
    (net (code "50") (name "unconnected-(J1-Pad7)") (class "Default")
      (node (ref "J1") (pin "7") (pinfunction "7_7") (pintype "passive+no_connect"))
    )
    (net (code "51") (name "unconnected-(J1-Pad9)") (class "Default")
      (node (ref "J1") (pin "9") (pinfunction "9_9") (pintype "passive+no_connect"))
    )
    (net (code "52") (name "unconnected-(P1-Pad12)") (class "Default")
      (node (ref "P1") (pin "12") (pinfunction "12_12") (pintype "passive+no_connect"))
    )
    (net (code "53") (name "unconnected-(P1-Pad35)") (class "Default")
      (node (ref "P1") (pin "35") (pinfunction "35_35") (pintype "passive+no_connect"))
    )
    (net (code "54") (name "unconnected-(P1-Pad46)") (class "Default")
      (node (ref "P1") (pin "46") (pinfunction "46_46") (pintype "passive+no_connect"))
    )
    (net (code "55") (name "unconnected-(U3-NC-Pad5)") (class "Default")
      (node (ref "U3") (pin "5") (pinfunction "NC_5") (pintype "passive+no_connect"))
    )
    (net (code "56") (name "unconnected-(U3-NC-Pad8)") (class "Default")
      (node (ref "U3") (pin "8") (pinfunction "NC_8") (pintype "passive+no_connect"))
    )
  )
)
